# moister-proto.net
KiCad netlist of a schematic drawn in EAGLE
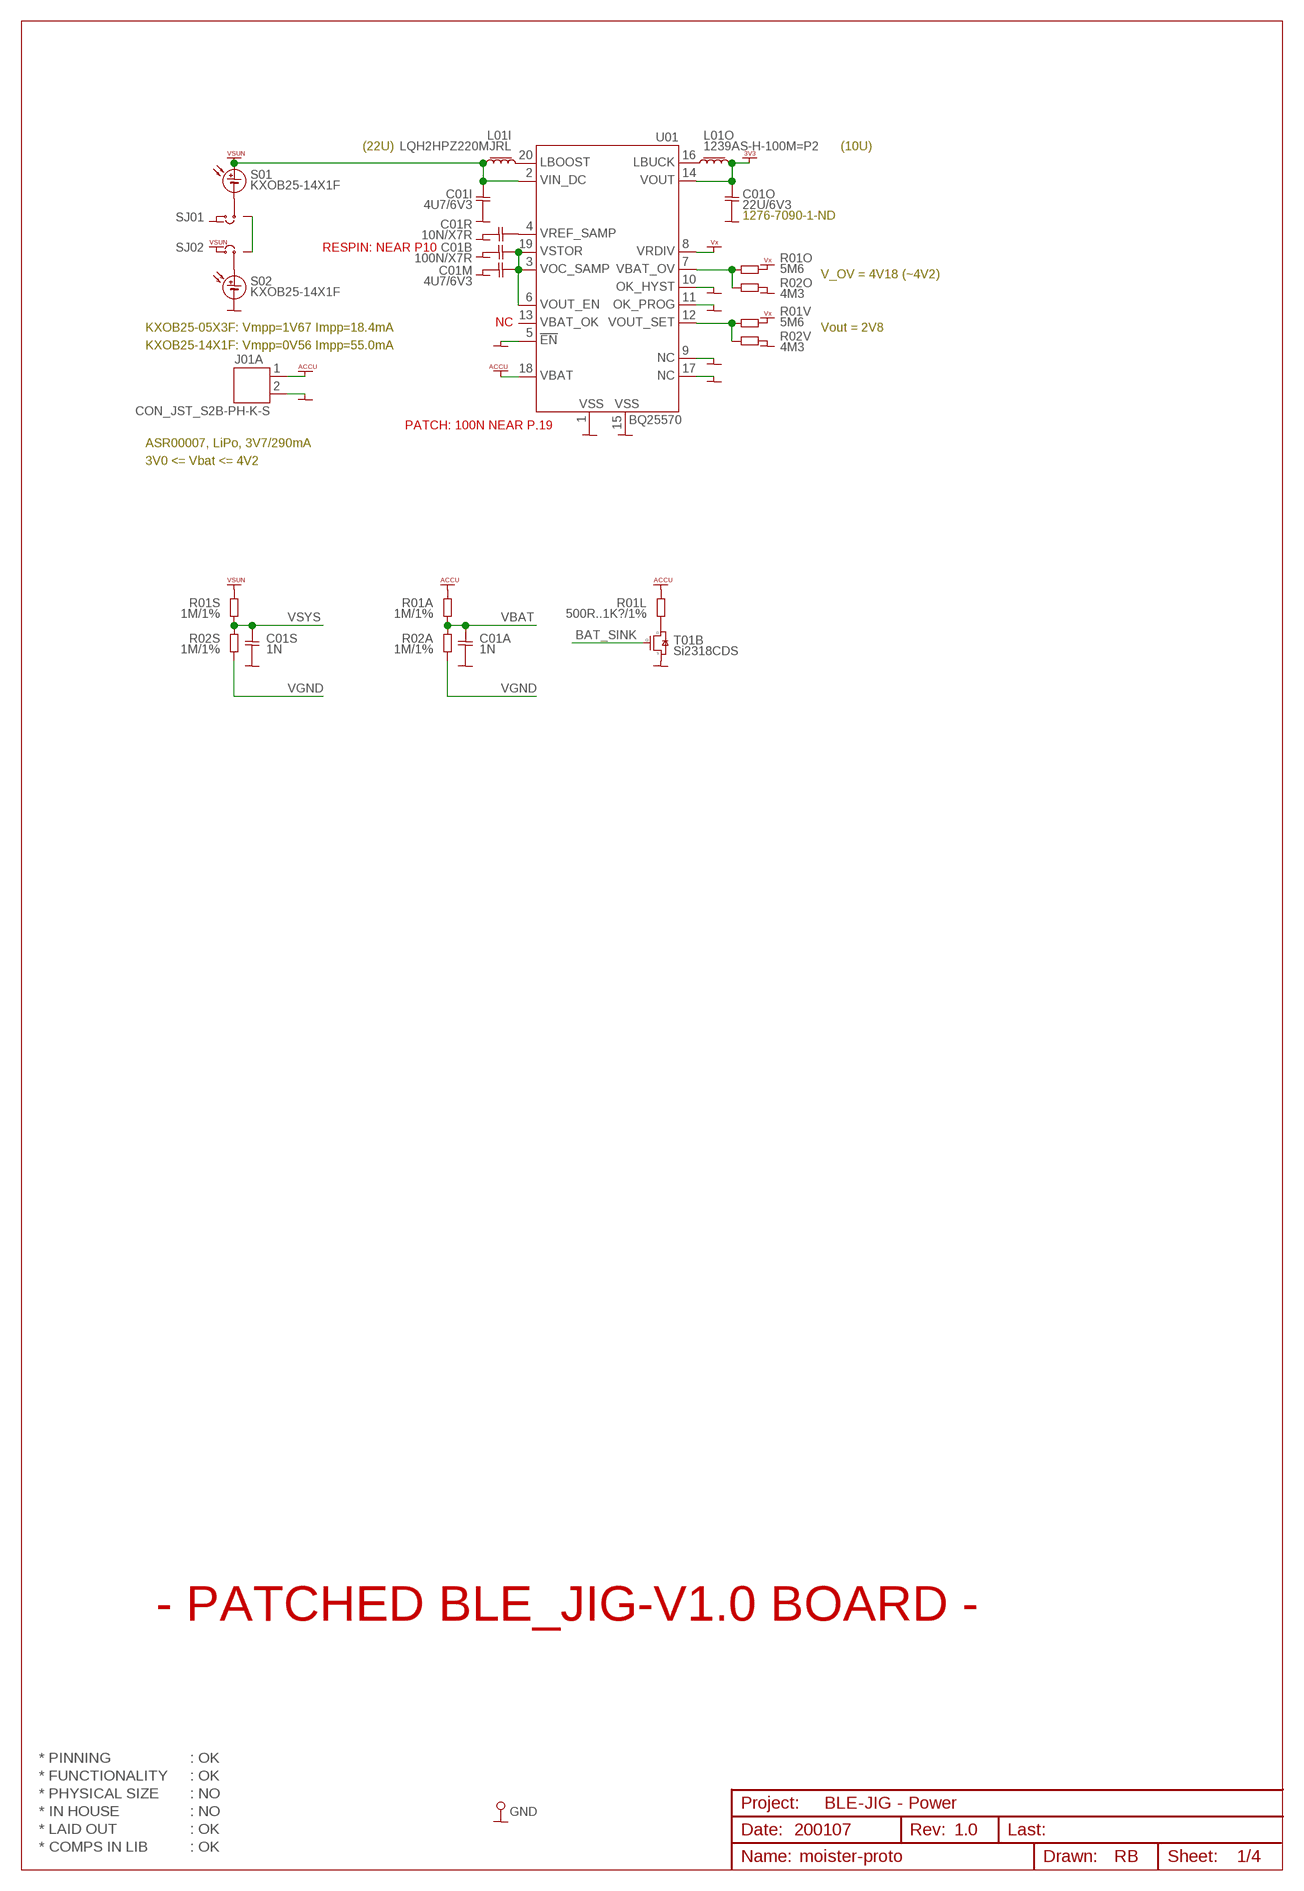
[diagram p0: schematic, sheet 1]
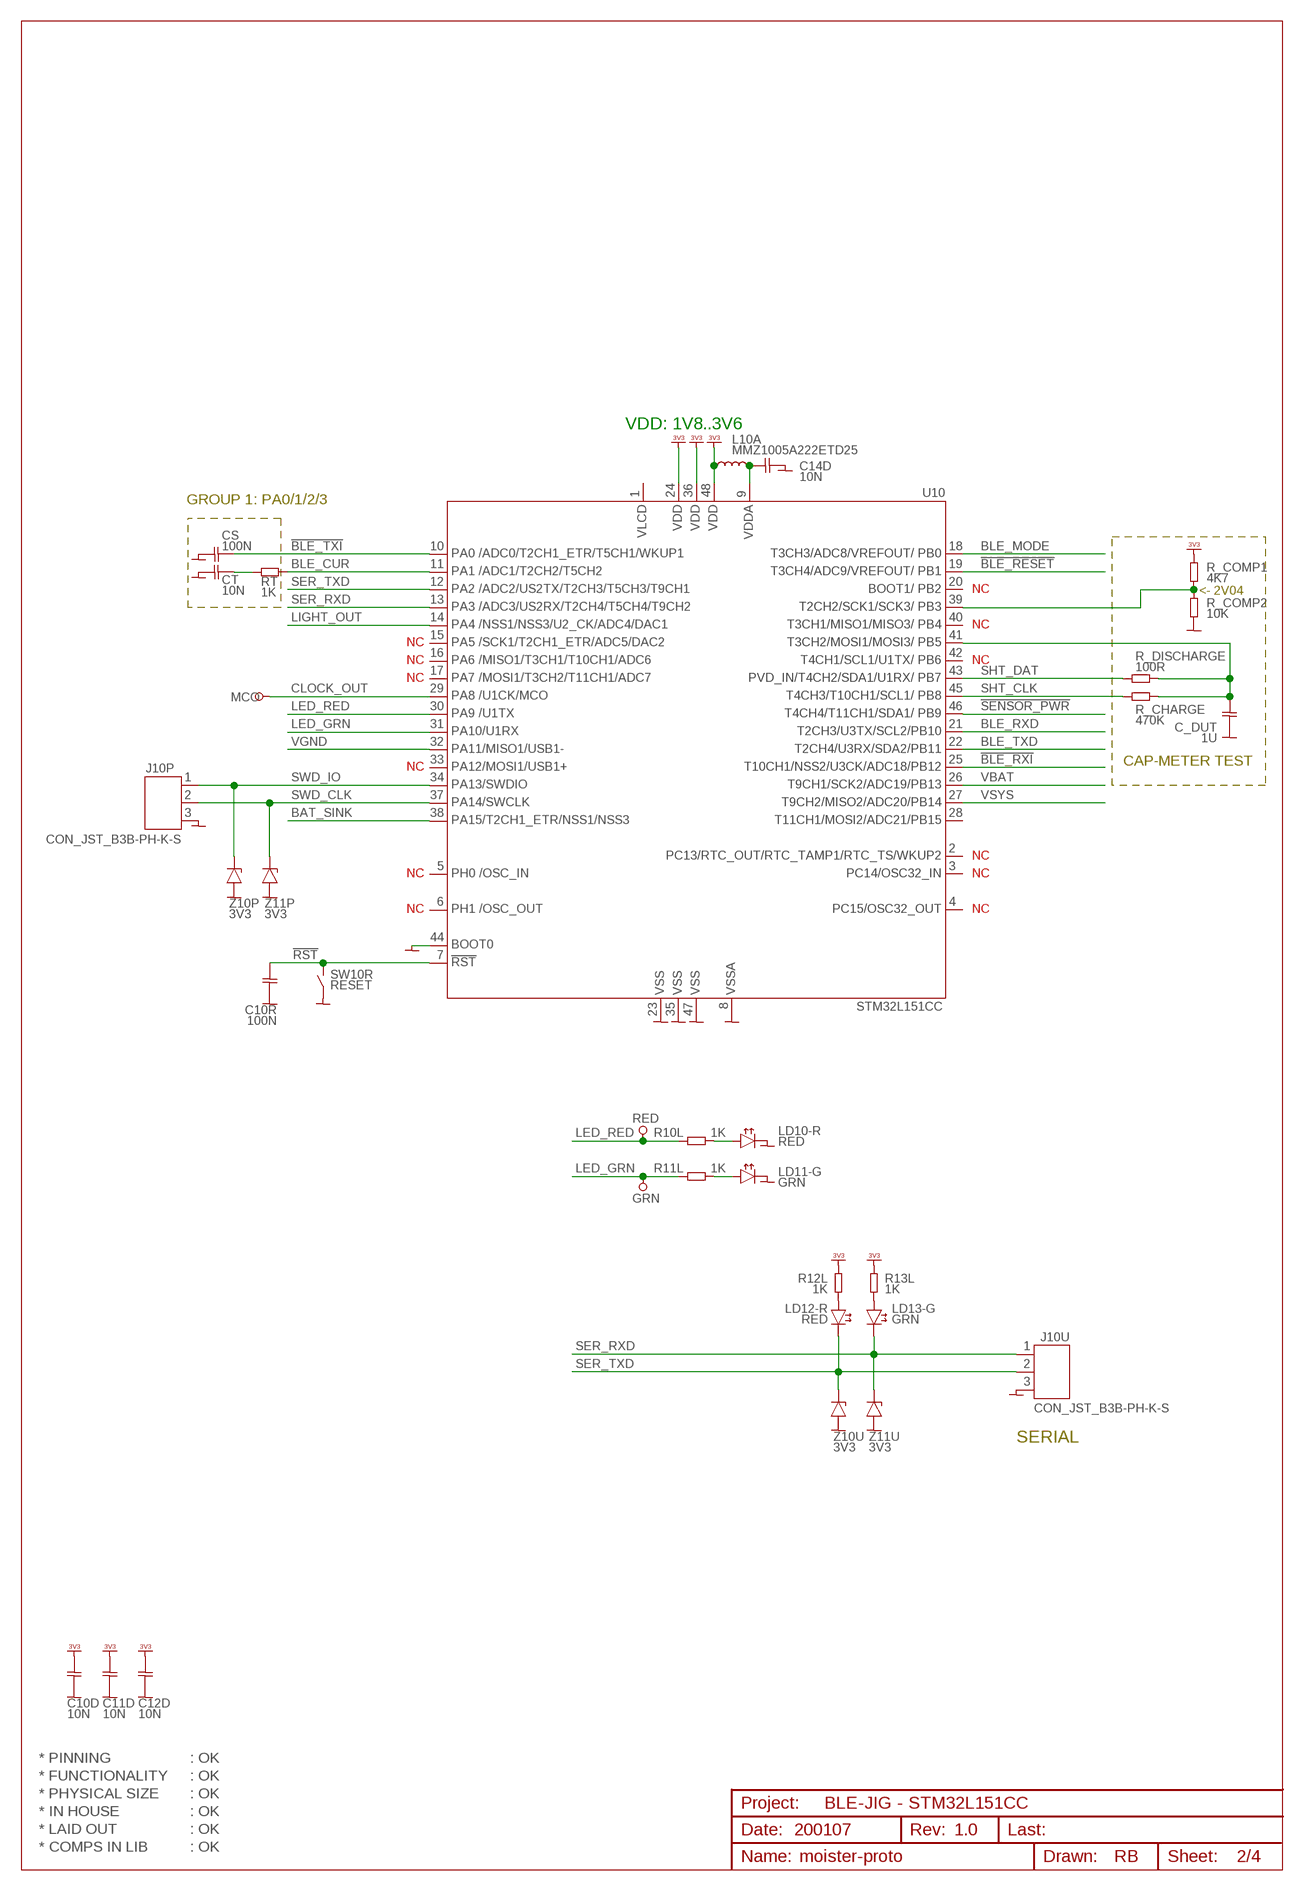
[diagram p1: schematic, sheet 2]
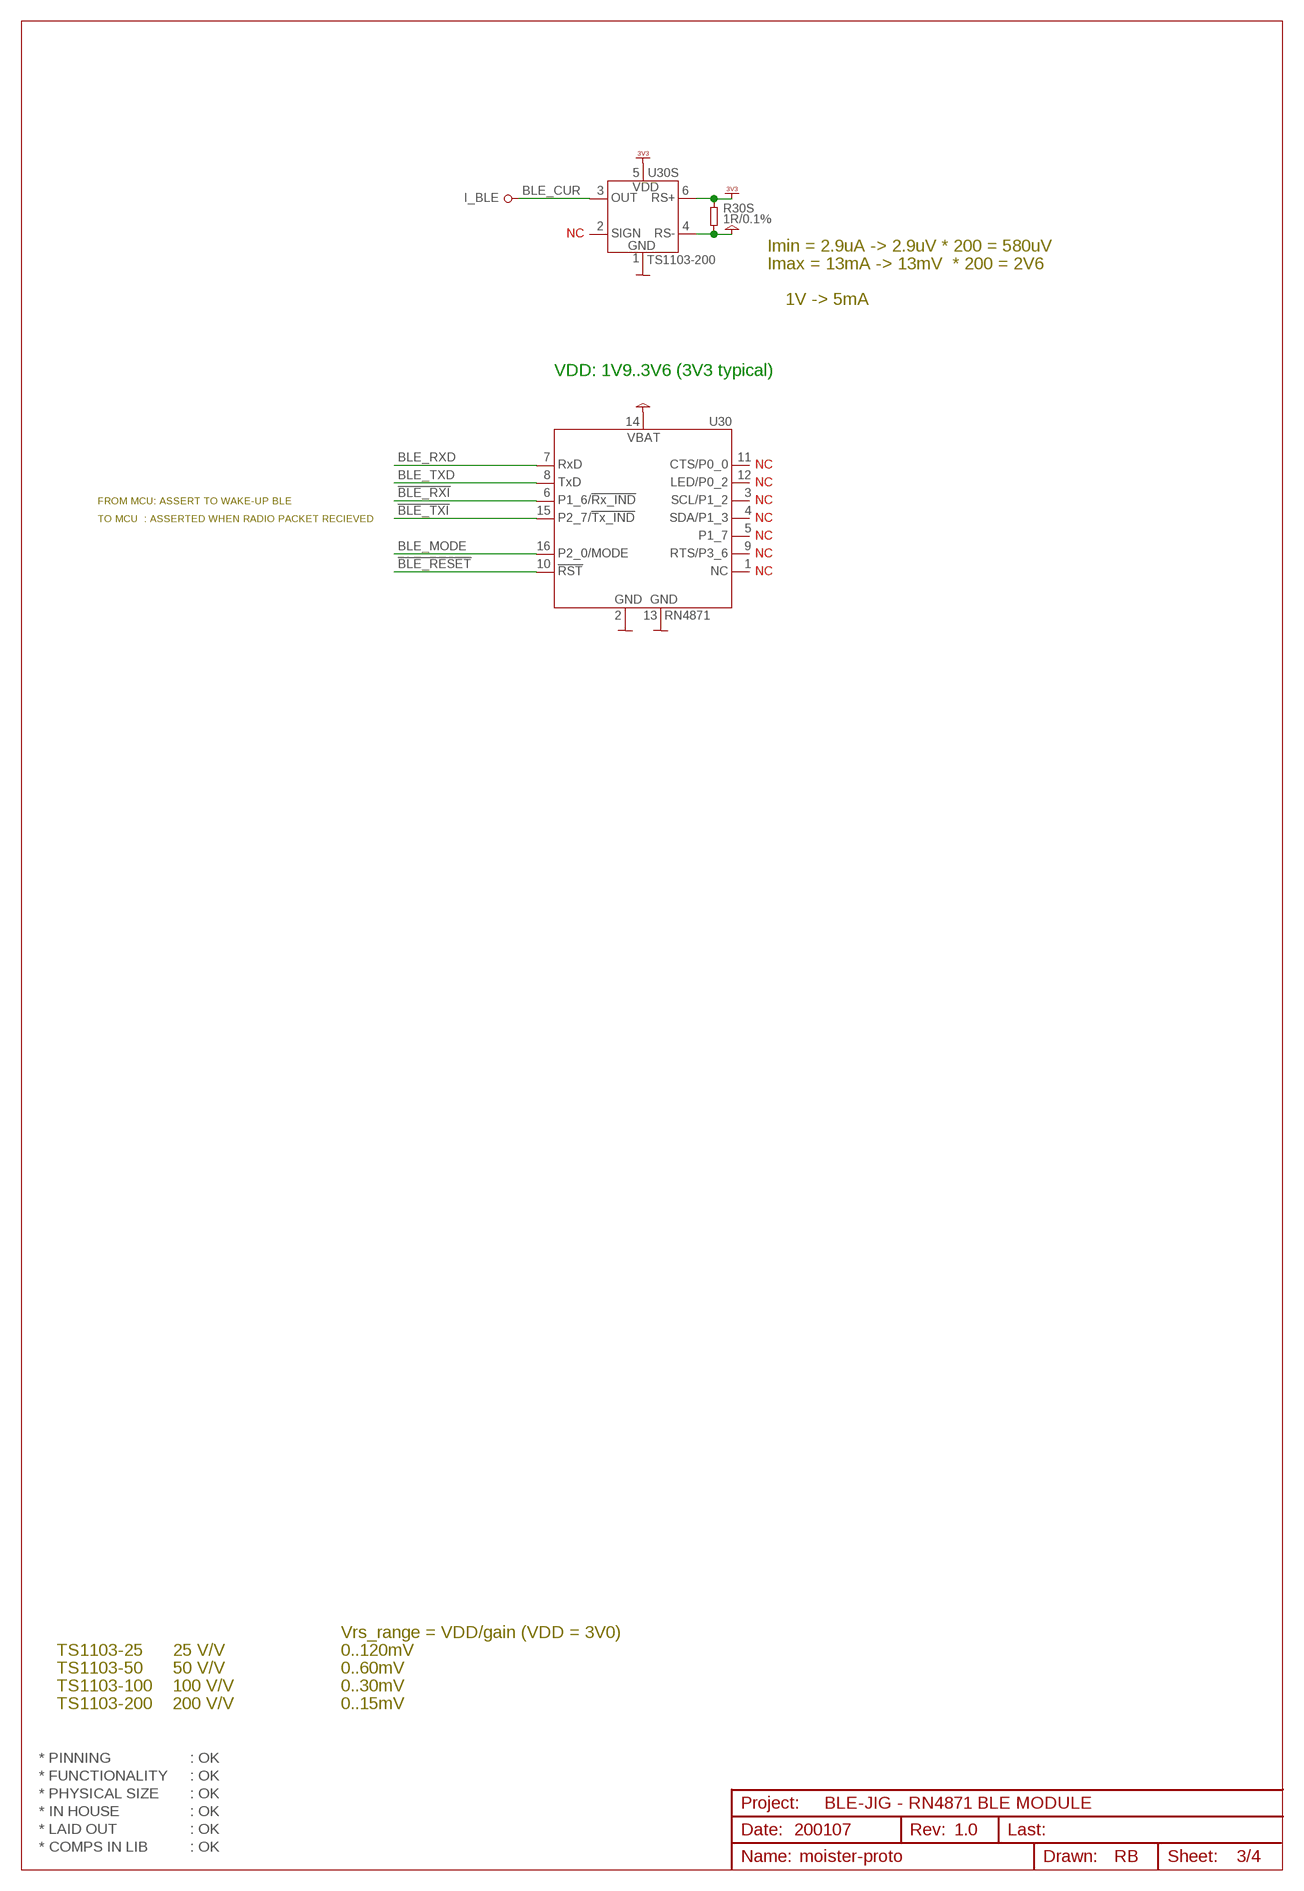
[diagram p2: schematic, sheet 3]
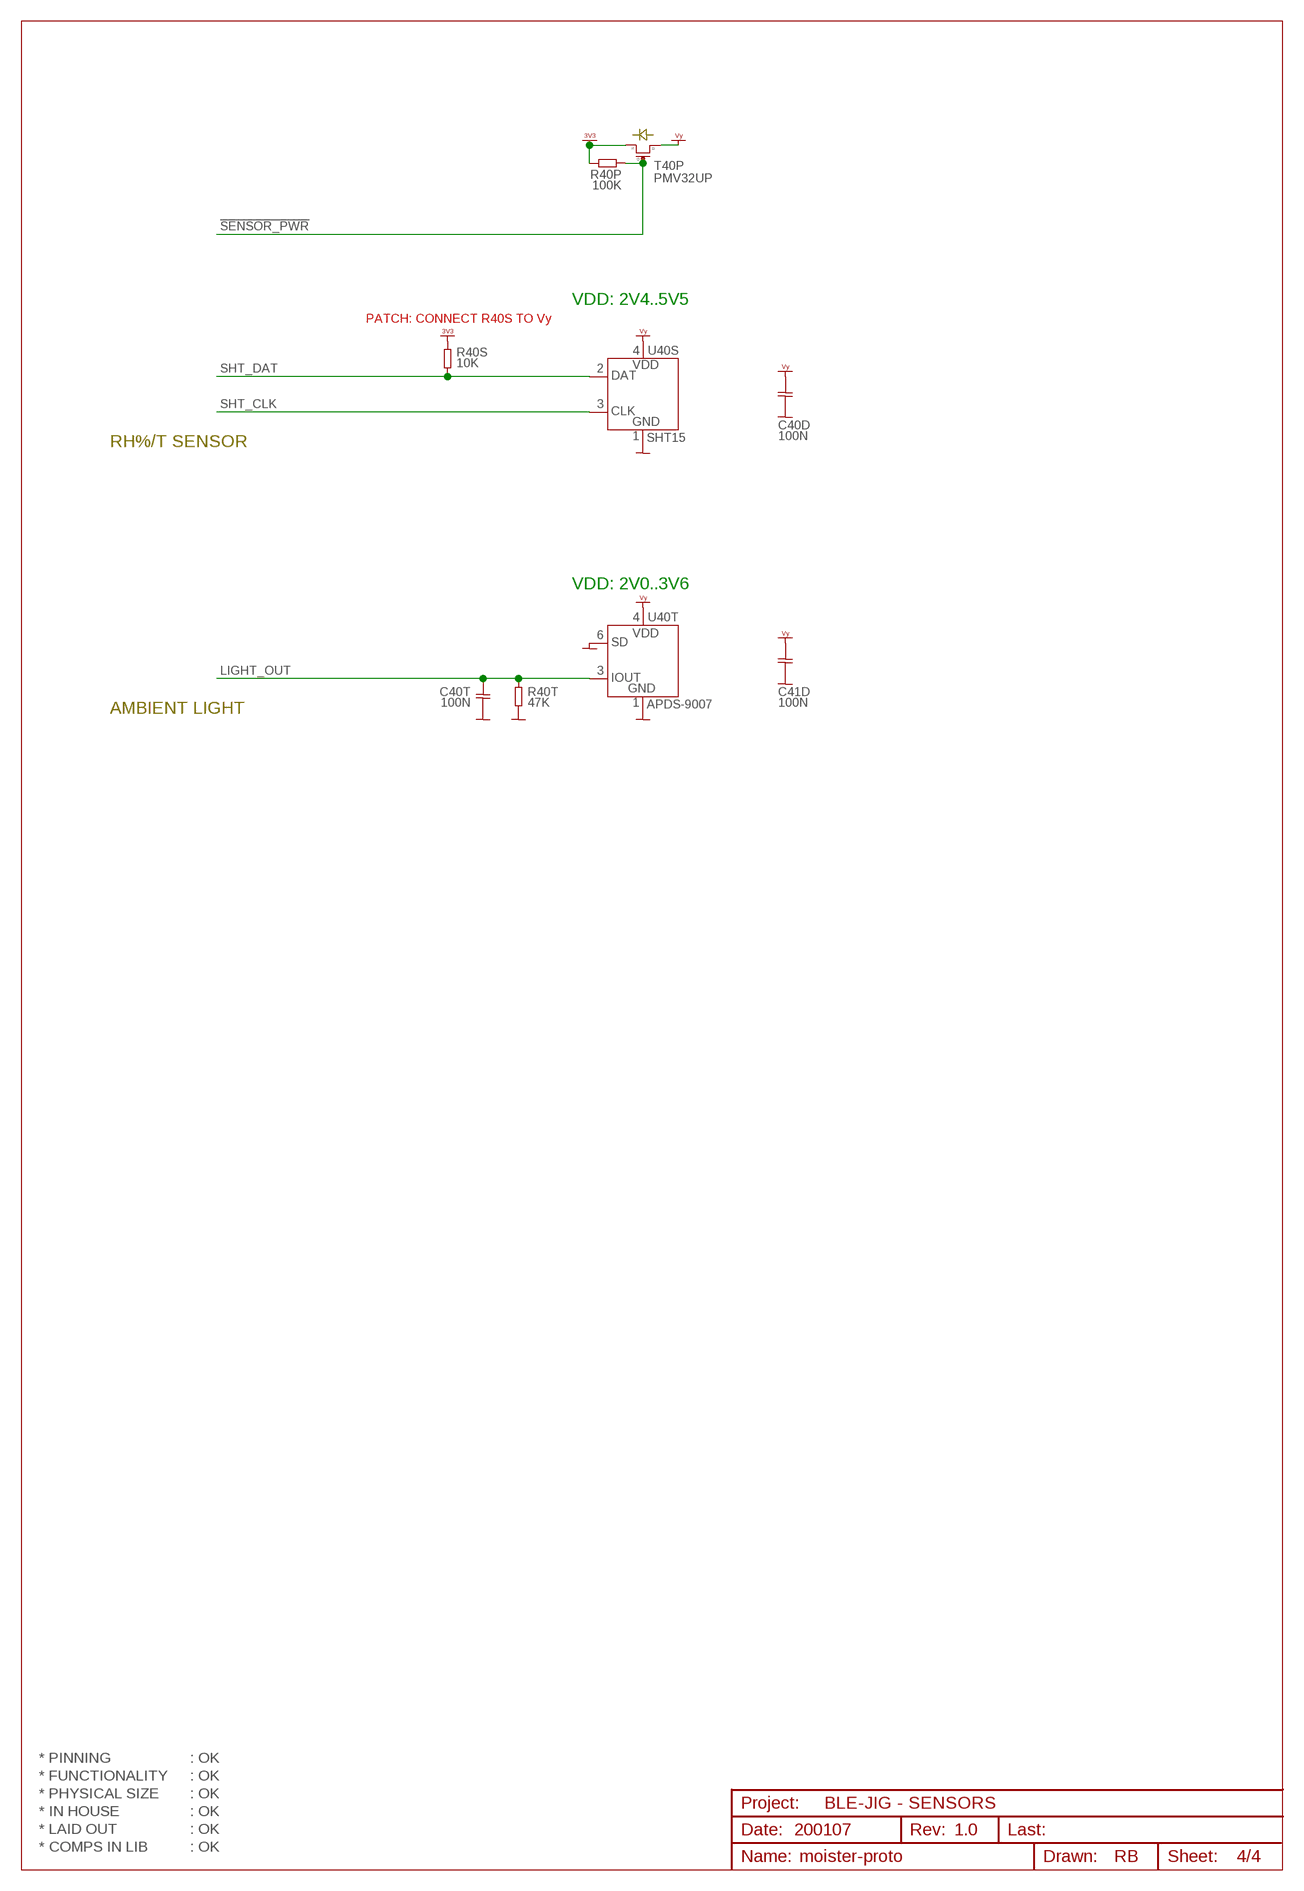
[diagram p3: schematic, sheet 4]

(export (version "E")
  (design (tool "Eeschema 10.0.6"))
  (components
    (comp (ref "I_BLE")
      (value "PIN_TEST")
      (footprint "eagle-import:HOLE_PTH_0.8MM")
      (libsource (lib "eagle-import") (part "PIN_TEST"))
    )
    (comp (ref "R30S")
      (value "1R/0.1%")
      (footprint "eagle-import:RES0603")
      (libsource (lib "eagle-import") (part "RES0603"))
    )
    (comp (ref "U30")
      (value "RN4871")
      (footprint "eagle-import:RN4871")
      (libsource (lib "eagle-import") (part "RN4871"))
    )
    (comp (ref "U30S")
      (value "TS1103-200")
      (footprint "eagle-import:SOT23-6")
      (libsource (lib "eagle-import") (part "TS1103-200"))
    )
    (comp (ref "C40D")
      (value "100N")
      (footprint "eagle-import:CAP0402")
      (libsource (lib "eagle-import") (part "CAP0402"))
    )
    (comp (ref "C40T")
      (value "100N")
      (footprint "eagle-import:CAP0402")
      (libsource (lib "eagle-import") (part "CAP0402"))
    )
    (comp (ref "C41D")
      (value "100N")
      (footprint "eagle-import:CAP0402")
      (libsource (lib "eagle-import") (part "CAP0402"))
    )
    (comp (ref "R40P")
      (value "100K")
      (footprint "eagle-import:RES0402")
      (libsource (lib "eagle-import") (part "RES0402"))
    )
    (comp (ref "R40S")
      (value "10K")
      (footprint "eagle-import:RES0402")
      (libsource (lib "eagle-import") (part "RES0402"))
    )
    (comp (ref "R40T")
      (value "47K")
      (footprint "eagle-import:RES0402")
      (libsource (lib "eagle-import") (part "RES0402"))
    )
    (comp (ref "T40P")
      (value "PMV32UP")
      (footprint "eagle-import:PFET_SOT23")
      (libsource (lib "eagle-import") (part "PFET_SOT23"))
    )
    (comp (ref "U40S")
      (value "SHT15")
      (footprint "eagle-import:SHT15")
      (libsource (lib "eagle-import") (part "SHT15"))
    )
    (comp (ref "U40T")
      (value "APDS-9007")
      (footprint "eagle-import:APDS-9007")
      (libsource (lib "eagle-import") (part "APDS-9007"))
    )
    (comp (ref "C01A")
      (value "1N")
      (footprint "eagle-import:CAP0402")
      (libsource (lib "eagle-import") (part "CAP0402"))
    )
    (comp (ref "C01B")
      (value "100N/X7R")
      (footprint "eagle-import:CAP0402")
      (libsource (lib "eagle-import") (part "CAP0402"))
    )
    (comp (ref "C01I")
      (value "4U7/6V3")
      (footprint "eagle-import:CAP0402")
      (libsource (lib "eagle-import") (part "CAP0402"))
    )
    (comp (ref "C01M")
      (value "4U7/6V3")
      (footprint "eagle-import:CAP0402")
      (libsource (lib "eagle-import") (part "CAP0402"))
    )
    (comp (ref "C01O")
      (value "22U/6V3")
      (footprint "eagle-import:CAP0402")
      (libsource (lib "eagle-import") (part "CAP0402"))
    )
    (comp (ref "C01R")
      (value "10N/X7R")
      (footprint "eagle-import:CAP0402")
      (libsource (lib "eagle-import") (part "CAP0402"))
    )
    (comp (ref "C01S")
      (value "1N")
      (footprint "eagle-import:CAP0402")
      (libsource (lib "eagle-import") (part "CAP0402"))
    )
    (comp (ref "GND")
      (value "PIN_TEST")
      (footprint "eagle-import:HOLE_PTH_0.8MM")
      (libsource (lib "eagle-import") (part "PIN_TEST"))
    )
    (comp (ref "J01A")
      (value "CON_JST_S2B-PH-K-S")
      (footprint "eagle-import:CON_JST_S2B-PH-K-S")
      (libsource (lib "eagle-import") (part "CON_JST_S2B-PH-K-S"))
    )
    (comp (ref "L01I")
      (value "LQH2HPZ220MJRL")
      (footprint "eagle-import:L_1008")
      (libsource (lib "eagle-import") (part "L_1008"))
    )
    (comp (ref "L01O")
      (value "1239AS-H-100M=P2")
      (footprint "eagle-import:L_1008")
      (libsource (lib "eagle-import") (part "L_1008"))
    )
    (comp (ref "R01A")
      (value "1M/1%")
      (footprint "eagle-import:RES0402")
      (libsource (lib "eagle-import") (part "RES0402"))
    )
    (comp (ref "R01L")
      (value "500R..1K?/1%")
      (footprint "eagle-import:RES0603")
      (libsource (lib "eagle-import") (part "RES0603"))
    )
    (comp (ref "R01O")
      (value "5M6")
      (footprint "eagle-import:RES0402")
      (libsource (lib "eagle-import") (part "RES0402"))
    )
    (comp (ref "R01S")
      (value "1M/1%")
      (footprint "eagle-import:RES0402")
      (libsource (lib "eagle-import") (part "RES0402"))
    )
    (comp (ref "R01V")
      (value "5M6")
      (footprint "eagle-import:RES0402")
      (libsource (lib "eagle-import") (part "RES0402"))
    )
    (comp (ref "R02A")
      (value "1M/1%")
      (footprint "eagle-import:RES0402")
      (libsource (lib "eagle-import") (part "RES0402"))
    )
    (comp (ref "R02O")
      (value "4M3")
      (footprint "eagle-import:RES0402")
      (libsource (lib "eagle-import") (part "RES0402"))
    )
    (comp (ref "R02S")
      (value "1M/1%")
      (footprint "eagle-import:RES0402")
      (libsource (lib "eagle-import") (part "RES0402"))
    )
    (comp (ref "R02V")
      (value "4M3")
      (footprint "eagle-import:RES0402")
      (libsource (lib "eagle-import") (part "RES0402"))
    )
    (comp (ref "S01")
      (value "KXOB25-14X1F")
      (footprint "eagle-import:KXOB25-14X1F")
      (libsource (lib "eagle-import") (part "KXOB25-14X1F"))
    )
    (comp (ref "S02")
      (value "KXOB25-14X1F")
      (footprint "eagle-import:KXOB25-14X1F")
      (libsource (lib "eagle-import") (part "KXOB25-14X1F"))
    )
    (comp (ref "SJ01")
      (value "SJ3SJ3-S")
      (footprint "eagle-import:SJ3-S")
      (libsource (lib "eagle-import") (part "SJ3SJ3-S"))
    )
    (comp (ref "SJ02")
      (value "SJ3SJ3-S")
      (footprint "eagle-import:SJ3-S")
      (libsource (lib "eagle-import") (part "SJ3SJ3-S"))
    )
    (comp (ref "T01B")
      (value "Si2318CDS")
      (footprint "eagle-import:NFET_SOT23")
      (libsource (lib "eagle-import") (part "NFET_SOT23"))
    )
    (comp (ref "U01")
      (value "BQ25570")
      (footprint "eagle-import:VQFN20")
      (libsource (lib "eagle-import") (part "BQ25570"))
    )
    (comp (ref "C10D")
      (value "10N")
      (footprint "eagle-import:CAP0402")
      (libsource (lib "eagle-import") (part "CAP0402"))
    )
    (comp (ref "C10R")
      (value "100N")
      (footprint "eagle-import:CAP0402")
      (libsource (lib "eagle-import") (part "CAP0402"))
    )
    (comp (ref "C11D")
      (value "10N")
      (footprint "eagle-import:CAP0402")
      (libsource (lib "eagle-import") (part "CAP0402"))
    )
    (comp (ref "C12D")
      (value "10N")
      (footprint "eagle-import:CAP0402")
      (libsource (lib "eagle-import") (part "CAP0402"))
    )
    (comp (ref "C14D")
      (value "10N")
      (footprint "eagle-import:CAP0402")
      (libsource (lib "eagle-import") (part "CAP0402"))
    )
    (comp (ref "CS")
      (value "100N")
      (footprint "eagle-import:CAP0805")
      (libsource (lib "eagle-import") (part "CAP0805"))
    )
    (comp (ref "CT")
      (value "10N")
      (footprint "eagle-import:CAP0805")
      (libsource (lib "eagle-import") (part "CAP0805"))
    )
    (comp (ref "C_DUT")
      (value "1U")
      (footprint "eagle-import:CAP0603")
      (libsource (lib "eagle-import") (part "CAP0603"))
    )
    (comp (ref "GRN")
      (value "PIN_TEST_0.6MM")
      (footprint "eagle-import:HOLE_PTH_0.6MM")
      (libsource (lib "eagle-import") (part "PIN_TEST_0.6MM"))
    )
    (comp (ref "J10P")
      (value "CON_JST_B3B-PH-K-S")
      (footprint "eagle-import:CON_JST_B3B-PH-K-S")
      (libsource (lib "eagle-import") (part "CON_JST_B3B-PH-K-S"))
    )
    (comp (ref "J10U")
      (value "CON_JST_B3B-PH-K-S")
      (footprint "eagle-import:CON_JST_B3B-PH-K-S")
      (libsource (lib "eagle-import") (part "CON_JST_B3B-PH-K-S"))
    )
    (comp (ref "L10A")
      (value "MMZ1005A222ETD25")
      (footprint "eagle-import:L_0402")
      (libsource (lib "eagle-import") (part "L_0402"))
    )
    (comp (ref "LD10-R")
      (value "RED")
      (footprint "eagle-import:LED_SMD_0603")
      (libsource (lib "eagle-import") (part "LED_SMD_0603"))
    )
    (comp (ref "LD11-G")
      (value "GRN")
      (footprint "eagle-import:LED_SMD_0603")
      (libsource (lib "eagle-import") (part "LED_SMD_0603"))
    )
    (comp (ref "LD12-R")
      (value "RED")
      (footprint "eagle-import:LED_SMD_0603")
      (libsource (lib "eagle-import") (part "LED_SMD_0603"))
    )
    (comp (ref "LD13-G")
      (value "GRN")
      (footprint "eagle-import:LED_SMD_0603")
      (libsource (lib "eagle-import") (part "LED_SMD_0603"))
    )
    (comp (ref "MCO")
      (value "PIN_TEST")
      (footprint "eagle-import:HOLE_PTH_0.8MM")
      (libsource (lib "eagle-import") (part "PIN_TEST"))
    )
    (comp (ref "R10L")
      (value "1K")
      (footprint "eagle-import:RES0402")
      (libsource (lib "eagle-import") (part "RES0402"))
    )
    (comp (ref "R11L")
      (value "1K")
      (footprint "eagle-import:RES0402")
      (libsource (lib "eagle-import") (part "RES0402"))
    )
    (comp (ref "R12L")
      (value "1K")
      (footprint "eagle-import:RES0402")
      (libsource (lib "eagle-import") (part "RES0402"))
    )
    (comp (ref "R13L")
      (value "1K")
      (footprint "eagle-import:RES0402")
      (libsource (lib "eagle-import") (part "RES0402"))
    )
    (comp (ref "RED")
      (value "PIN_TEST_0.6MM")
      (footprint "eagle-import:HOLE_PTH_0.6MM")
      (libsource (lib "eagle-import") (part "PIN_TEST_0.6MM"))
    )
    (comp (ref "RT")
      (value "1K")
      (footprint "eagle-import:RES0805")
      (libsource (lib "eagle-import") (part "RES0805"))
    )
    (comp (ref "R_CHARGE")
      (value "470K")
      (footprint "eagle-import:RES0603")
      (libsource (lib "eagle-import") (part "RES0603"))
    )
    (comp (ref "R_COMP1")
      (value "4K7")
      (footprint "eagle-import:RES0603")
      (libsource (lib "eagle-import") (part "RES0603"))
    )
    (comp (ref "R_COMP2")
      (value "10K")
      (footprint "eagle-import:RES0603")
      (libsource (lib "eagle-import") (part "RES0603"))
    )
    (comp (ref "R_DISCHARGE")
      (value "100R")
      (footprint "eagle-import:RES0603")
      (libsource (lib "eagle-import") (part "RES0603"))
    )
    (comp (ref "SW10R")
      (value "RESET")
      (footprint "eagle-import:SWITCH_PUSHBUTTON_EVP-AVAA1A")
      (libsource (lib "eagle-import") (part "SWITCH_PUSHBUTTON_EVP-AVAA1A"))
    )
    (comp (ref "U10")
      (value "STM32L151CC")
      (footprint "eagle-import:LQFP48")
      (libsource (lib "eagle-import") (part "STM32L151CC"))
    )
    (comp (ref "Z10P")
      (value "3V3")
      (footprint "eagle-import:ZENER_SOD80")
      (libsource (lib "eagle-import") (part "ZENER_SOD80"))
    )
    (comp (ref "Z10U")
      (value "3V3")
      (footprint "eagle-import:ZENER_SOD80")
      (libsource (lib "eagle-import") (part "ZENER_SOD80"))
    )
    (comp (ref "Z11P")
      (value "3V3")
      (footprint "eagle-import:ZENER_SOD80")
      (libsource (lib "eagle-import") (part "ZENER_SOD80"))
    )
    (comp (ref "Z11U")
      (value "3V3")
      (footprint "eagle-import:ZENER_SOD80")
      (libsource (lib "eagle-import") (part "ZENER_SOD80"))
    )
  )
  (nets
    (net (code "1") (name "ACCU") (class "Default")
      (node (ref "J01A") (pin "1") (pinfunction "1_1") (pintype "passive"))
      (node (ref "R01A") (pin "2") (pinfunction "2_2") (pintype "passive"))
      (node (ref "R01L") (pin "2") (pinfunction "2_2") (pintype "passive"))
      (node (ref "U01") (pin "18") (pinfunction "18.VBAT_18") (pintype "passive"))
    )
    (net (code "2") (name "BAT_SINK") (class "Default")
      (node (ref "T01B") (pin "1") (pinfunction "G1_1") (pintype "bidirectional"))
      (node (ref "U10") (pin "38") (pinfunction "38.PA15_38") (pintype "passive"))
    )
    (net (code "3") (name "BLE_CUR") (class "Default")
      (node (ref "I_BLE") (pin "1") (pinfunction "P$1_1") (pintype "passive"))
      (node (ref "RT") (pin "1") (pinfunction "1_1") (pintype "passive"))
      (node (ref "U10") (pin "11") (pinfunction "11.PA1_11") (pintype "passive"))
      (node (ref "U30S") (pin "3") (pinfunction "3.OUT_3") (pintype "passive"))
    )
    (net (code "4") (name "BLE_MODE") (class "Default")
      (node (ref "U10") (pin "18") (pinfunction "18.PB0_18") (pintype "passive"))
      (node (ref "U30") (pin "16") (pinfunction "16.P2_0_16") (pintype "passive"))
    )
    (net (code "5") (name "BLE_RXD") (class "Default")
      (node (ref "U10") (pin "21") (pinfunction "21.PB10_21") (pintype "passive"))
      (node (ref "U30") (pin "7") (pinfunction "7.RXD_7") (pintype "passive"))
    )
    (net (code "6") (name "BLE_TXD") (class "Default")
      (node (ref "U10") (pin "22") (pinfunction "22.PB11_22") (pintype "passive"))
      (node (ref "U30") (pin "8") (pinfunction "8.TXD_8") (pintype "passive"))
    )
    (net (code "7") (name "CLOCK_OUT") (class "Default")
      (node (ref "MCO") (pin "1") (pinfunction "P$1_1") (pintype "passive"))
      (node (ref "U10") (pin "29") (pinfunction "29.PA8_29") (pintype "passive"))
    )
    (net (code "8") (name "GND") (class "Default")
      (node (ref "C01A") (pin "2") (pinfunction "2_2") (pintype "passive"))
      (node (ref "C01B") (pin "2") (pinfunction "2_2") (pintype "passive"))
      (node (ref "C01I") (pin "2") (pinfunction "2_2") (pintype "passive"))
      (node (ref "C01M") (pin "2") (pinfunction "2_2") (pintype "passive"))
      (node (ref "C01O") (pin "2") (pinfunction "2_2") (pintype "passive"))
      (node (ref "C01R") (pin "2") (pinfunction "2_2") (pintype "passive"))
      (node (ref "C01S") (pin "2") (pinfunction "2_2") (pintype "passive"))
      (node (ref "C10D") (pin "2") (pinfunction "2_2") (pintype "passive"))
      (node (ref "C10R") (pin "2") (pinfunction "2_2") (pintype "passive"))
      (node (ref "C11D") (pin "2") (pinfunction "2_2") (pintype "passive"))
      (node (ref "C12D") (pin "2") (pinfunction "2_2") (pintype "passive"))
      (node (ref "C14D") (pin "2") (pinfunction "2_2") (pintype "passive"))
      (node (ref "C40D") (pin "2") (pinfunction "2_2") (pintype "passive"))
      (node (ref "C40T") (pin "2") (pinfunction "2_2") (pintype "passive"))
      (node (ref "C41D") (pin "2") (pinfunction "2_2") (pintype "passive"))
      (node (ref "CS") (pin "1") (pinfunction "1_1") (pintype "passive"))
      (node (ref "CT") (pin "1") (pinfunction "1_1") (pintype "passive"))
      (node (ref "C_DUT") (pin "2") (pinfunction "2_2") (pintype "passive"))
      (node (ref "GND") (pin "1") (pinfunction "P$1_1") (pintype "passive"))
      (node (ref "J01A") (pin "2") (pinfunction "2_2") (pintype "passive"))
      (node (ref "J10P") (pin "3") (pinfunction "3_3") (pintype "passive"))
      (node (ref "J10U") (pin "3") (pinfunction "3_3") (pintype "passive"))
      (node (ref "LD10-R") (pin "C") (pinfunction "C_C") (pintype "passive"))
      (node (ref "LD11-G") (pin "C") (pinfunction "C_C") (pintype "passive"))
      (node (ref "R02O") (pin "2") (pinfunction "2_2") (pintype "passive"))
      (node (ref "R02V") (pin "2") (pinfunction "2_2") (pintype "passive"))
      (node (ref "R40T") (pin "2") (pinfunction "2_2") (pintype "passive"))
      (node (ref "R_COMP2") (pin "2") (pinfunction "2_2") (pintype "passive"))
      (node (ref "S02") (pin "2") (pinfunction "2_2") (pintype "passive"))
      (node (ref "SJ01") (pin "1") (pinfunction "1_1") (pintype "passive"))
      (node (ref "SW10R") (pin "2") (pinfunction "3-4_2") (pintype "passive"))
      (node (ref "T01B") (pin "2") (pinfunction "S2_2") (pintype "bidirectional"))
      (node (ref "U01") (pin "1") (pinfunction "1.VSS_1") (pintype "passive"))
      (node (ref "U01") (pin "10") (pinfunction "10.OK_HYST_10") (pintype "passive"))
      (node (ref "U01") (pin "11") (pinfunction "11.OK_PROG_11") (pintype "passive"))
      (node (ref "U01") (pin "15") (pinfunction "15.VSS_15") (pintype "passive"))
      (node (ref "U01") (pin "17") (pinfunction "17.NC_17") (pintype "passive"))
      (node (ref "U01") (pin "5") (pinfunction "5.~{EN}_5") (pintype "passive"))
      (node (ref "U01") (pin "9") (pinfunction "9.NC_9") (pintype "passive"))
      (node (ref "U01") (pin "TP") (pinfunction "15.VSS_TP") (pintype "passive"))
      (node (ref "U01") (pin "V1") (pinfunction "15.VSS_V1") (pintype "passive"))
      (node (ref "U01") (pin "V2") (pinfunction "15.VSS_V2") (pintype "passive"))
      (node (ref "U01") (pin "V3") (pinfunction "15.VSS_V3") (pintype "passive"))
      (node (ref "U01") (pin "V4") (pinfunction "15.VSS_V4") (pintype "passive"))
      (node (ref "U10") (pin "23") (pinfunction "23.GND_23") (pintype "passive"))
      (node (ref "U10") (pin "35") (pinfunction "35.GND_35") (pintype "passive"))
      (node (ref "U10") (pin "44") (pinfunction "44.BOOT0_44") (pintype "passive"))
      (node (ref "U10") (pin "47") (pinfunction "47.GND_47") (pintype "passive"))
      (node (ref "U10") (pin "8") (pinfunction "8.GND_8") (pintype "passive"))
      (node (ref "U30") (pin "13") (pinfunction "13.GND_13") (pintype "passive"))
      (node (ref "U30") (pin "2") (pinfunction "2.GND_2") (pintype "passive"))
      (node (ref "U30S") (pin "1") (pinfunction "1.GND_1") (pintype "passive"))
      (node (ref "U40S") (pin "1") (pinfunction "1.GND_1") (pintype "passive"))
      (node (ref "U40T") (pin "1") (pinfunction "1.GND_1") (pintype "passive"))
      (node (ref "U40T") (pin "6") (pinfunction "6.SD_6") (pintype "passive"))
      (node (ref "Z10P") (pin "1") (pinfunction "A_1") (pintype "passive"))
      (node (ref "Z10U") (pin "1") (pinfunction "A_1") (pintype "passive"))
      (node (ref "Z11P") (pin "1") (pinfunction "A_1") (pintype "passive"))
      (node (ref "Z11U") (pin "1") (pinfunction "A_1") (pintype "passive"))
    )
    (net (code "9") (name "LED_GRN") (class "Default")
      (node (ref "GRN") (pin "1") (pinfunction "P$1_1") (pintype "passive"))
      (node (ref "R11L") (pin "1") (pinfunction "1_1") (pintype "passive"))
      (node (ref "U10") (pin "31") (pinfunction "31.PA10_31") (pintype "passive"))
    )
    (net (code "10") (name "LED_RED") (class "Default")
      (node (ref "R10L") (pin "1") (pinfunction "1_1") (pintype "passive"))
      (node (ref "RED") (pin "1") (pinfunction "P$1_1") (pintype "passive"))
      (node (ref "U10") (pin "30") (pinfunction "30.PA9_30") (pintype "passive"))
    )
    (net (code "11") (name "LIGHT_OUT") (class "Default")
      (node (ref "C40T") (pin "1") (pinfunction "1_1") (pintype "passive"))
      (node (ref "R40T") (pin "1") (pinfunction "1_1") (pintype "passive"))
      (node (ref "U10") (pin "14") (pinfunction "14.PA4_14") (pintype "passive"))
      (node (ref "U40T") (pin "3") (pinfunction "3.IOUT_3") (pintype "passive"))
    )
    (net (code "12") (name "Net-(CT-Pad2)") (class "Default")
      (node (ref "CT") (pin "2") (pinfunction "2_2") (pintype "passive"))
      (node (ref "RT") (pin "2") (pinfunction "2_2") (pintype "passive"))
    )
    (net (code "13") (name "Net-(LD10-R-PadA)") (class "Default")
      (node (ref "LD10-R") (pin "A") (pinfunction "A_A") (pintype "passive"))
      (node (ref "R10L") (pin "2") (pinfunction "2_2") (pintype "passive"))
    )
    (net (code "14") (name "Net-(LD11-G-PadA)") (class "Default")
      (node (ref "LD11-G") (pin "A") (pinfunction "A_A") (pintype "passive"))
      (node (ref "R11L") (pin "2") (pinfunction "2_2") (pintype "passive"))
    )
    (net (code "15") (name "Net-(LD12-R-PadA)") (class "Default")
      (node (ref "LD12-R") (pin "A") (pinfunction "A_A") (pintype "passive"))
      (node (ref "R12L") (pin "2") (pinfunction "2_2") (pintype "passive"))
    )
    (net (code "16") (name "Net-(LD13-G-PadA)") (class "Default")
      (node (ref "LD13-G") (pin "A") (pinfunction "A_A") (pintype "passive"))
      (node (ref "R13L") (pin "2") (pinfunction "2_2") (pintype "passive"))
    )
    (net (code "17") (name "Net-(S01-Pad2)") (class "Default")
      (node (ref "S01") (pin "2") (pinfunction "2_2") (pintype "passive"))
      (node (ref "SJ01") (pin "2") (pinfunction "2_2") (pintype "passive"))
    )
    (net (code "18") (name "Net-(S02-Pad1)") (class "Default")
      (node (ref "S02") (pin "1") (pinfunction "1_1") (pintype "passive"))
      (node (ref "SJ02") (pin "2") (pinfunction "2_2") (pintype "passive"))
    )
    (net (code "19") (name "Net-(SJ01-Pad3)") (class "Default")
      (node (ref "SJ01") (pin "3") (pinfunction "3_3") (pintype "passive"))
      (node (ref "SJ02") (pin "3") (pinfunction "3_3") (pintype "passive"))
    )
    (net (code "20") (name "Net-(T01B-D3)") (class "Default")
      (node (ref "R01L") (pin "1") (pinfunction "1_1") (pintype "passive"))
      (node (ref "T01B") (pin "3") (pinfunction "D3_3") (pintype "bidirectional"))
    )
    (net (code "21") (name "Net-(U01-4.VREF_SAMP)") (class "Default")
      (node (ref "C01R") (pin "1") (pinfunction "1_1") (pintype "passive"))
      (node (ref "U01") (pin "4") (pinfunction "4.VREF_SAMP_4") (pintype "passive"))
    )
    (net (code "22") (name "Net-(U01-7.VBAT_OV)") (class "Default")
      (node (ref "R01O") (pin "2") (pinfunction "2_2") (pintype "passive"))
      (node (ref "R02O") (pin "1") (pinfunction "1_1") (pintype "passive"))
      (node (ref "U01") (pin "7") (pinfunction "7.VBAT_OV_7") (pintype "passive"))
    )
    (net (code "23") (name "Net-(U01-12.VOUT_SET)") (class "Default")
      (node (ref "R01V") (pin "2") (pinfunction "2_2") (pintype "passive"))
      (node (ref "R02V") (pin "1") (pinfunction "1_1") (pintype "passive"))
      (node (ref "U01") (pin "12") (pinfunction "12.VOUT_SET_12") (pintype "passive"))
    )
    (net (code "24") (name "Net-(U01-16.LBUCK)") (class "Default")
      (node (ref "L01O") (pin "1") (pinfunction "1_1") (pintype "passive"))
      (node (ref "U01") (pin "16") (pinfunction "16.LBUCK_16") (pintype "passive"))
    )
    (net (code "25") (name "Net-(U01-19.VSTOR)") (class "Default")
      (node (ref "C01B") (pin "1") (pinfunction "1_1") (pintype "passive"))
      (node (ref "C01M") (pin "1") (pinfunction "1_1") (pintype "passive"))
      (node (ref "U01") (pin "19") (pinfunction "19.VSTOR_19") (pintype "passive"))
      (node (ref "U01") (pin "3") (pinfunction "3.VOC_SAMP_3") (pintype "passive"))
      (node (ref "U01") (pin "6") (pinfunction "6.VOUT_EN_6") (pintype "passive"))
    )
    (net (code "26") (name "Net-(U01-20.LBOOST)") (class "Default")
      (node (ref "L01I") (pin "2") (pinfunction "2_2") (pintype "passive"))
      (node (ref "U01") (pin "20") (pinfunction "20.LBOOST_20") (pintype "passive"))
    )
    (net (code "27") (name "Net-(U10-9.VDD)") (class "Default")
      (node (ref "C14D") (pin "1") (pinfunction "1_1") (pintype "passive"))
      (node (ref "L10A") (pin "2") (pinfunction "2_2") (pintype "passive"))
      (node (ref "U10") (pin "9") (pinfunction "9.VDD_9") (pintype "passive"))
    )
    (net (code "28") (name "Net-(U10-39.PB3)") (class "Default")
      (node (ref "R_COMP1") (pin "2") (pinfunction "2_2") (pintype "passive"))
      (node (ref "R_COMP2") (pin "1") (pinfunction "1_1") (pintype "passive"))
      (node (ref "U10") (pin "39") (pinfunction "39.PB3_39") (pintype "passive"))
    )
    (net (code "29") (name "Net-(U10-41.PB5)") (class "Default")
      (node (ref "C_DUT") (pin "1") (pinfunction "1_1") (pintype "passive"))
      (node (ref "R_CHARGE") (pin "2") (pinfunction "2_2") (pintype "passive"))
      (node (ref "R_DISCHARGE") (pin "2") (pinfunction "2_2") (pintype "passive"))
      (node (ref "U10") (pin "41") (pinfunction "41.PB5_41") (pintype "passive"))
    )
    (net (code "30") (name "SER_RXD") (class "Default")
      (node (ref "J10U") (pin "1") (pinfunction "1_1") (pintype "passive"))
      (node (ref "LD13-G") (pin "C") (pinfunction "C_C") (pintype "passive"))
      (node (ref "U10") (pin "13") (pinfunction "13.PA3_13") (pintype "passive"))
      (node (ref "Z11U") (pin "2") (pinfunction "C_2") (pintype "passive"))
    )
    (net (code "31") (name "SER_TXD") (class "Default")
      (node (ref "J10U") (pin "2") (pinfunction "2_2") (pintype "passive"))
      (node (ref "LD12-R") (pin "C") (pinfunction "C_C") (pintype "passive"))
      (node (ref "U10") (pin "12") (pinfunction "12.PA2_12") (pintype "passive"))
      (node (ref "Z10U") (pin "2") (pinfunction "C_2") (pintype "passive"))
    )
    (net (code "32") (name "SHT_CLK") (class "Default")
      (node (ref "R_CHARGE") (pin "1") (pinfunction "1_1") (pintype "passive"))
      (node (ref "U10") (pin "45") (pinfunction "45.PB8_45") (pintype "passive"))
      (node (ref "U40S") (pin "3") (pinfunction "3.CLK_3") (pintype "passive"))
    )
    (net (code "33") (name "SHT_DAT") (class "Default")
      (node (ref "R40S") (pin "2") (pinfunction "2_2") (pintype "passive"))
      (node (ref "R_DISCHARGE") (pin "1") (pinfunction "1_1") (pintype "passive"))
      (node (ref "U10") (pin "43") (pinfunction "43.PB7_43") (pintype "passive"))
      (node (ref "U40S") (pin "2") (pinfunction "2.DAT_2") (pintype "passive"))
    )
    (net (code "34") (name "SWD_CLK") (class "Default")
      (node (ref "J10P") (pin "2") (pinfunction "2_2") (pintype "passive"))
      (node (ref "U10") (pin "37") (pinfunction "37.PA14_37") (pintype "passive"))
      (node (ref "Z11P") (pin "2") (pinfunction "C_2") (pintype "passive"))
    )
    (net (code "35") (name "SWD_IO") (class "Default")
      (node (ref "J10P") (pin "1") (pinfunction "1_1") (pintype "passive"))
      (node (ref "U10") (pin "34") (pinfunction "34.PA13_34") (pintype "passive"))
      (node (ref "Z10P") (pin "2") (pinfunction "C_2") (pintype "passive"))
    )
    (net (code "36") (name "VBAT") (class "Default")
      (node (ref "C01A") (pin "1") (pinfunction "1_1") (pintype "passive"))
      (node (ref "R01A") (pin "1") (pinfunction "1_1") (pintype "passive"))
      (node (ref "R02A") (pin "2") (pinfunction "2_2") (pintype "passive"))
      (node (ref "U10") (pin "26") (pinfunction "26.PB13_26") (pintype "passive"))
    )
    (net (code "37") (name "VCC") (class "Default")
      (node (ref "R30S") (pin "2") (pinfunction "2_2") (pintype "passive"))
      (node (ref "U30") (pin "14") (pinfunction "14.VBAT_14") (pintype "passive"))
      (node (ref "U30S") (pin "4") (pinfunction "4.RS-_4") (pintype "passive"))
    )
    (net (code "38") (name "VDD_3V3") (class "Default")
      (node (ref "C01O") (pin "1") (pinfunction "1_1") (pintype "passive"))
      (node (ref "C10D") (pin "1") (pinfunction "1_1") (pintype "passive"))
      (node (ref "C11D") (pin "1") (pinfunction "1_1") (pintype "passive"))
      (node (ref "C12D") (pin "1") (pinfunction "1_1") (pintype "passive"))
      (node (ref "L01O") (pin "2") (pinfunction "2_2") (pintype "passive"))
      (node (ref "L10A") (pin "1") (pinfunction "1_1") (pintype "passive"))
      (node (ref "R12L") (pin "1") (pinfunction "1_1") (pintype "passive"))
      (node (ref "R13L") (pin "1") (pinfunction "1_1") (pintype "passive"))
      (node (ref "R30S") (pin "1") (pinfunction "1_1") (pintype "passive"))
      (node (ref "R40P") (pin "1") (pinfunction "1_1") (pintype "passive"))
      (node (ref "R40S") (pin "1") (pinfunction "1_1") (pintype "passive"))
      (node (ref "R_COMP1") (pin "1") (pinfunction "1_1") (pintype "passive"))
      (node (ref "T40P") (pin "2") (pinfunction "S_2") (pintype "bidirectional"))
      (node (ref "U01") (pin "14") (pinfunction "14.VOUT_14") (pintype "passive"))
      (node (ref "U10") (pin "24") (pinfunction "24.VDD_24") (pintype "passive"))
      (node (ref "U10") (pin "36") (pinfunction "36.VDD_36") (pintype "passive"))
      (node (ref "U10") (pin "48") (pinfunction "48.VDD_48") (pintype "passive"))
      (node (ref "U30S") (pin "5") (pinfunction "5.VDD_5") (pintype "passive"))
      (node (ref "U30S") (pin "6") (pinfunction "6.RS+_6") (pintype "passive"))
    )
    (net (code "39") (name "VGND") (class "Default")
      (node (ref "R02A") (pin "1") (pinfunction "1_1") (pintype "passive"))
      (node (ref "R02S") (pin "1") (pinfunction "1_1") (pintype "passive"))
      (node (ref "U10") (pin "32") (pinfunction "32.PA11_32") (pintype "passive"))
    )
    (net (code "40") (name "VSUN") (class "Default")
      (node (ref "C01I") (pin "1") (pinfunction "1_1") (pintype "passive"))
      (node (ref "L01I") (pin "1") (pinfunction "1_1") (pintype "passive"))
      (node (ref "R01S") (pin "2") (pinfunction "2_2") (pintype "passive"))
      (node (ref "S01") (pin "1") (pinfunction "1_1") (pintype "passive"))
      (node (ref "SJ02") (pin "1") (pinfunction "1_1") (pintype "passive"))
      (node (ref "U01") (pin "2") (pinfunction "2.VIN_DC_2") (pintype "passive"))
    )
    (net (code "41") (name "VSYS") (class "Default")
      (node (ref "C01S") (pin "1") (pinfunction "1_1") (pintype "passive"))
      (node (ref "R01S") (pin "1") (pinfunction "1_1") (pintype "passive"))
      (node (ref "R02S") (pin "2") (pinfunction "2_2") (pintype "passive"))
      (node (ref "U10") (pin "27") (pinfunction "27.PB14_27") (pintype "passive"))
    )
    (net (code "42") (name "VX") (class "Default")
      (node (ref "R01O") (pin "1") (pinfunction "1_1") (pintype "passive"))
      (node (ref "R01V") (pin "1") (pinfunction "1_1") (pintype "passive"))
      (node (ref "U01") (pin "8") (pinfunction "8.VRDIV_8") (pintype "passive"))
    )
    (net (code "43") (name "VY") (class "Default")
      (node (ref "C40D") (pin "1") (pinfunction "1_1") (pintype "passive"))
      (node (ref "C41D") (pin "1") (pinfunction "1_1") (pintype "passive"))
      (node (ref "T40P") (pin "3") (pinfunction "D_3") (pintype "bidirectional"))
      (node (ref "U40S") (pin "4") (pinfunction "4.VDD_4") (pintype "passive"))
      (node (ref "U40T") (pin "4") (pinfunction "4.VDD_4") (pintype "passive"))
    )
    (net (code "44") (name "unconnected-(U01-13.VBAT_OK-Pad13)") (class "Default")
      (node (ref "U01") (pin "13") (pinfunction "13.VBAT_OK_13") (pintype "passive"))
    )
    (net (code "45") (name "unconnected-(U10-1.VDD-Pad1)") (class "Default")
      (node (ref "U10") (pin "1") (pinfunction "1.VDD_1") (pintype "passive"))
    )
    (net (code "46") (name "unconnected-(U10-2.PC13-Pad2)") (class "Default")
      (node (ref "U10") (pin "2") (pinfunction "2.PC13_2") (pintype "passive"))
    )
    (net (code "47") (name "unconnected-(U10-3.PC14-Pad3)") (class "Default")
      (node (ref "U10") (pin "3") (pinfunction "3.PC14_3") (pintype "passive"))
    )
    (net (code "48") (name "unconnected-(U10-4.PC15-Pad4)") (class "Default")
      (node (ref "U10") (pin "4") (pinfunction "4.PC15_4") (pintype "passive"))
    )
    (net (code "49") (name "unconnected-(U10-5.OSC_IN-Pad5)") (class "Default")
      (node (ref "U10") (pin "5") (pinfunction "5.OSC_IN_5") (pintype "passive"))
    )
    (net (code "50") (name "unconnected-(U10-6.OSC_OUT-Pad6)") (class "Default")
      (node (ref "U10") (pin "6") (pinfunction "6.OSC_OUT_6") (pintype "passive"))
    )
    (net (code "51") (name "unconnected-(U10-15.PA5-Pad15)") (class "Default")
      (node (ref "U10") (pin "15") (pinfunction "15.PA5_15") (pintype "passive"))
    )
    (net (code "52") (name "unconnected-(U10-16.PA6-Pad16)") (class "Default")
      (node (ref "U10") (pin "16") (pinfunction "16.PA6_16") (pintype "passive"))
    )
    (net (code "53") (name "unconnected-(U10-17.PA7-Pad17)") (class "Default")
      (node (ref "U10") (pin "17") (pinfunction "17.PA7_17") (pintype "passive"))
    )
    (net (code "54") (name "unconnected-(U10-20.PB2-Pad20)") (class "Default")
      (node (ref "U10") (pin "20") (pinfunction "20.PB2_20") (pintype "passive"))
    )
    (net (code "55") (name "unconnected-(U10-28.PB15-Pad28)") (class "Default")
      (node (ref "U10") (pin "28") (pinfunction "28.PB15_28") (pintype "passive"))
    )
    (net (code "56") (name "unconnected-(U10-33.PA12-Pad33)") (class "Default")
      (node (ref "U10") (pin "33") (pinfunction "33.PA12_33") (pintype "passive"))
    )
    (net (code "57") (name "unconnected-(U10-40.PB4-Pad40)") (class "Default")
      (node (ref "U10") (pin "40") (pinfunction "40.PB4_40") (pintype "passive"))
    )
    (net (code "58") (name "unconnected-(U10-42.PB6-Pad42)") (class "Default")
      (node (ref "U10") (pin "42") (pinfunction "42.PB6_42") (pintype "passive"))
    )
    (net (code "59") (name "unconnected-(U30-1.NC-Pad1)") (class "Default")
      (node (ref "U30") (pin "1") (pinfunction "1.NC_1") (pintype "passive"))
    )
    (net (code "60") (name "unconnected-(U30-3.P1_2-Pad3)") (class "Default")
      (node (ref "U30") (pin "3") (pinfunction "3.P1_2_3") (pintype "passive"))
    )
    (net (code "61") (name "unconnected-(U30-4.P1_3-Pad4)") (class "Default")
      (node (ref "U30") (pin "4") (pinfunction "4.P1_3_4") (pintype "passive"))
    )
    (net (code "62") (name "unconnected-(U30-5.P1_7-Pad5)") (class "Default")
      (node (ref "U30") (pin "5") (pinfunction "5.P1_7_5") (pintype "passive"))
    )
    (net (code "63") (name "unconnected-(U30-9.P3_6-Pad9)") (class "Default")
      (node (ref "U30") (pin "9") (pinfunction "9.P3_6_9") (pintype "passive"))
    )
    (net (code "64") (name "unconnected-(U30-11.P0_0-Pad11)") (class "Default")
      (node (ref "U30") (pin "11") (pinfunction "11.P0_0_11") (pintype "passive"))
    )
    (net (code "65") (name "unconnected-(U30-12.P0_2-Pad12)") (class "Default")
      (node (ref "U30") (pin "12") (pinfunction "12.P0_2_12") (pintype "passive"))
    )
    (net (code "66") (name "unconnected-(U30S-2.SIGN-Pad2)") (class "Default")
      (node (ref "U30S") (pin "2") (pinfunction "2.SIGN_2") (pintype "passive"))
    )
    (net (code "67") (name "~{BLE_RESET}") (class "Default")
      (node (ref "U10") (pin "19") (pinfunction "19.PB1_19") (pintype "passive"))
      (node (ref "U30") (pin "10") (pinfunction "10.~{RST}_10") (pintype "passive"))
    )
    (net (code "68") (name "~{BLE_RXI}") (class "Default")
      (node (ref "U10") (pin "25") (pinfunction "25.PB12_25") (pintype "passive"))
      (node (ref "U30") (pin "6") (pinfunction "6.P1_6_6") (pintype "passive"))
    )
    (net (code "69") (name "~{BLE_TXI}") (class "Default")
      (node (ref "CS") (pin "2") (pinfunction "2_2") (pintype "passive"))
      (node (ref "U10") (pin "10") (pinfunction "10.PA0_10") (pintype "passive"))
      (node (ref "U30") (pin "15") (pinfunction "15.P2_7_15") (pintype "passive"))
    )
    (net (code "70") (name "~{RST}") (class "Default")
      (node (ref "C10R") (pin "1") (pinfunction "1_1") (pintype "passive"))
      (node (ref "SW10R") (pin "1") (pinfunction "1-2_1") (pintype "passive"))
      (node (ref "U10") (pin "7") (pinfunction "7.~{RST}_7") (pintype "passive"))
    )
    (net (code "71") (name "~{SENSOR_PWR}") (class "Default")
      (node (ref "R40P") (pin "2") (pinfunction "2_2") (pintype "passive"))
      (node (ref "T40P") (pin "1") (pinfunction "G_1") (pintype "bidirectional"))
      (node (ref "U10") (pin "46") (pinfunction "46.PB9_46") (pintype "passive"))
    )
  )
)
